# shield.net
KiCad netlist of a schematic drawn in EAGLE
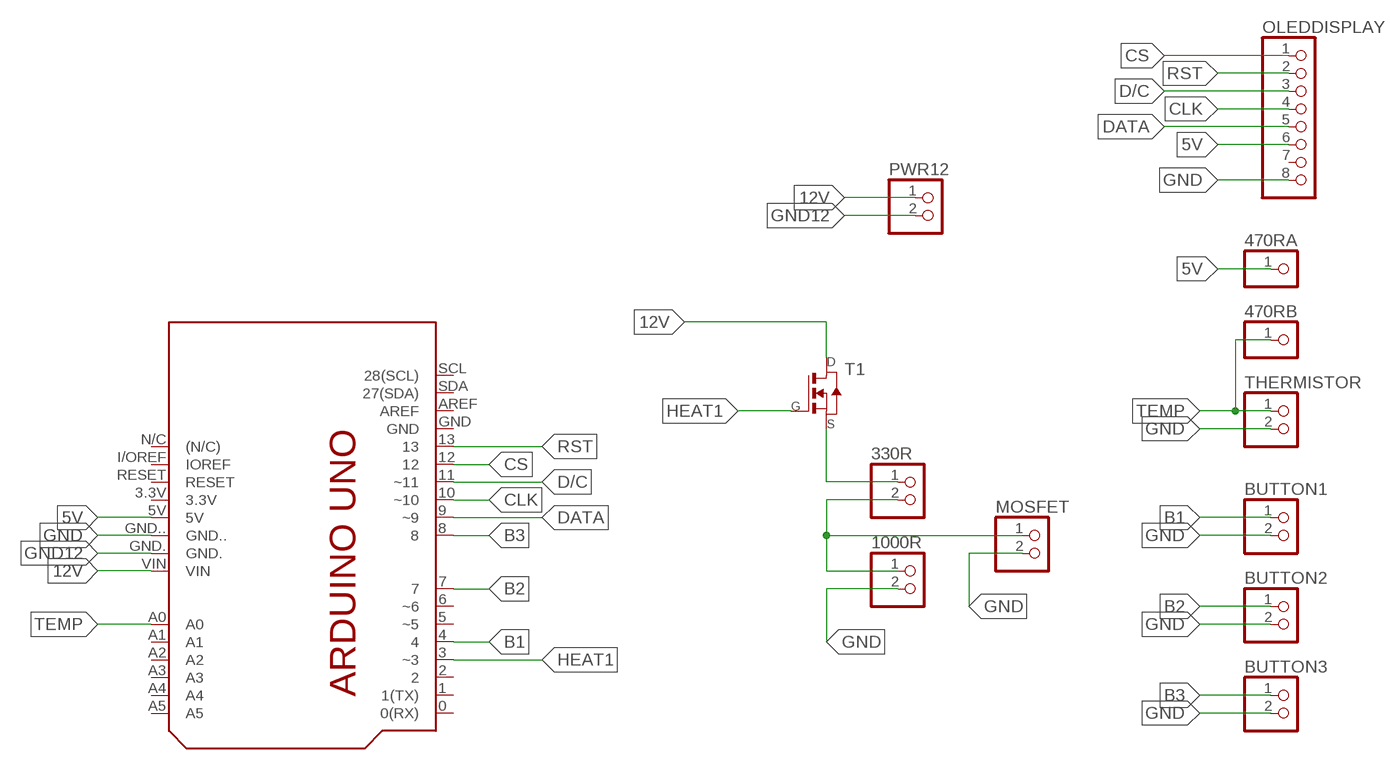
[diagram p0: schematic, sheet 1]

(export (version "E")
  (design (tool "Eeschema 10.0.6"))
  (components
    (comp (ref "330R")
      (value "PINHD-1X2")
      (footprint "eagle-import:1X02")
      (libsource (lib "eagle-import") (part "PINHD-1X2"))
    )
    (comp (ref "470RA")
      (value "PINHD-1X1")
      (footprint "eagle-import:1X01")
      (libsource (lib "eagle-import") (part "PINHD-1X1"))
    )
    (comp (ref "470RB")
      (value "PINHD-1X1")
      (footprint "eagle-import:1X01")
      (libsource (lib "eagle-import") (part "PINHD-1X1"))
    )
    (comp (ref "1000R")
      (value "PINHD-1X2")
      (footprint "eagle-import:1X02")
      (libsource (lib "eagle-import") (part "PINHD-1X2"))
    )
    (comp (ref "BUTTON1")
      (value "PINHD-1X2")
      (footprint "eagle-import:1X02")
      (libsource (lib "eagle-import") (part "PINHD-1X2"))
    )
    (comp (ref "BUTTON2")
      (value "PINHD-1X2")
      (footprint "eagle-import:1X02")
      (libsource (lib "eagle-import") (part "PINHD-1X2"))
    )
    (comp (ref "BUTTON3")
      (value "PINHD-1X2")
      (footprint "eagle-import:1X02")
      (libsource (lib "eagle-import") (part "PINHD-1X2"))
    )
    (comp (ref "MOSFET")
      (value "PINHD-1X2")
      (footprint "eagle-import:1X02")
      (libsource (lib "eagle-import") (part "PINHD-1X2"))
    )
    (comp (ref "OLEDDISPLAY")
      (value "PINHD-1X8")
      (footprint "eagle-import:1X08")
      (libsource (lib "eagle-import") (part "PINHD-1X8"))
    )
    (comp (ref "PCB1")
      (value "ARDUINO_UNO_UNBOUND")
      (footprint "eagle-import:ARDUINO_UNO_UNBOUND")
      (libsource (lib "eagle-import") (part "ARDUINO_UNO_UNBOUND"))
    )
    (comp (ref "PWR12")
      (value "PINHD-1X2")
      (footprint "eagle-import:1X02")
      (libsource (lib "eagle-import") (part "PINHD-1X2"))
    )
    (comp (ref "T1")
      (value "NMOSFETTO252")
      (footprint "eagle-import:TO252")
      (libsource (lib "eagle-import") (part "NMOSFETTO252"))
    )
    (comp (ref "THERMISTOR")
      (value "PINHD-1X2")
      (footprint "eagle-import:1X02")
      (libsource (lib "eagle-import") (part "PINHD-1X2"))
    )
  )
  (nets
    (net (code "1") (name "5V") (class "Default")
      (node (ref "470RA") (pin "1") (pinfunction "1_1") (pintype "passive"))
      (node (ref "OLEDDISPLAY") (pin "6") (pinfunction "6_6") (pintype "passive"))
      (node (ref "PCB1") (pin "5V") (pinfunction "5V_5V") (pintype "bidirectional"))
    )
    (net (code "2") (name "12V") (class "Default")
      (node (ref "PCB1") (pin "VIN") (pinfunction "VIN_VIN") (pintype "bidirectional"))
      (node (ref "PWR12") (pin "1") (pinfunction "1_1") (pintype "passive"))
      (node (ref "T1") (pin "3") (pinfunction "D_3") (pintype "passive"))
    )
    (net (code "3") (name "B1") (class "Default")
      (node (ref "BUTTON1") (pin "1") (pinfunction "1_1") (pintype "passive"))
      (node (ref "PCB1") (pin "4") (pinfunction "4_4") (pintype "bidirectional"))
    )
    (net (code "4") (name "B2") (class "Default")
      (node (ref "BUTTON2") (pin "1") (pinfunction "1_1") (pintype "passive"))
      (node (ref "PCB1") (pin "7") (pinfunction "7_7") (pintype "bidirectional"))
    )
    (net (code "5") (name "B3") (class "Default")
      (node (ref "BUTTON3") (pin "1") (pinfunction "1_1") (pintype "passive"))
      (node (ref "PCB1") (pin "8") (pinfunction "8_8") (pintype "bidirectional"))
    )
    (net (code "6") (name "CLK") (class "Default")
      (node (ref "OLEDDISPLAY") (pin "4") (pinfunction "4_4") (pintype "passive"))
      (node (ref "PCB1") (pin "10") (pinfunction "~{10}_10") (pintype "bidirectional"))
    )
    (net (code "7") (name "CS") (class "Default")
      (node (ref "OLEDDISPLAY") (pin "1") (pinfunction "1_1") (pintype "passive"))
      (node (ref "PCB1") (pin "12") (pinfunction "12_12") (pintype "bidirectional"))
    )
    (net (code "8") (name "DATA") (class "Default")
      (node (ref "OLEDDISPLAY") (pin "5") (pinfunction "5_5") (pintype "passive"))
      (node (ref "PCB1") (pin "9") (pinfunction "~{9}_9") (pintype "bidirectional"))
    )
    (net (code "9") (name "D{slash}C") (class "Default")
      (node (ref "OLEDDISPLAY") (pin "3") (pinfunction "3_3") (pintype "passive"))
      (node (ref "PCB1") (pin "11") (pinfunction "~{11}_11") (pintype "bidirectional"))
    )
    (net (code "10") (name "GND") (class "Default")
      (node (ref "1000R") (pin "2") (pinfunction "2_2") (pintype "passive"))
      (node (ref "BUTTON1") (pin "2") (pinfunction "2_2") (pintype "passive"))
      (node (ref "BUTTON2") (pin "2") (pinfunction "2_2") (pintype "passive"))
      (node (ref "BUTTON3") (pin "2") (pinfunction "2_2") (pintype "passive"))
      (node (ref "MOSFET") (pin "2") (pinfunction "2_2") (pintype "passive"))
      (node (ref "OLEDDISPLAY") (pin "8") (pinfunction "8_8") (pintype "passive"))
      (node (ref "PCB1") (pin "GND..") (pinfunction "GND.._GND..") (pintype "bidirectional"))
      (node (ref "THERMISTOR") (pin "2") (pinfunction "2_2") (pintype "passive"))
    )
    (net (code "11") (name "GND12") (class "Default")
      (node (ref "PCB1") (pin "GND.") (pinfunction "GND._GND.") (pintype "bidirectional"))
      (node (ref "PWR12") (pin "2") (pinfunction "2_2") (pintype "passive"))
    )
    (net (code "12") (name "HEAT1") (class "Default")
      (node (ref "PCB1") (pin "3") (pinfunction "~{3}_3") (pintype "bidirectional"))
      (node (ref "T1") (pin "1") (pinfunction "G_1") (pintype "passive"))
    )
    (net (code "13") (name "Net-(1000R-Pad1)") (class "Default")
      (node (ref "1000R") (pin "1") (pinfunction "1_1") (pintype "passive"))
      (node (ref "330R") (pin "2") (pinfunction "2_2") (pintype "passive"))
      (node (ref "MOSFET") (pin "1") (pinfunction "1_1") (pintype "passive"))
    )
    (net (code "14") (name "Net-(T1-S)") (class "Default")
      (node (ref "330R") (pin "1") (pinfunction "1_1") (pintype "passive"))
      (node (ref "T1") (pin "2") (pinfunction "S_2") (pintype "passive"))
    )
    (net (code "15") (name "RST") (class "Default")
      (node (ref "OLEDDISPLAY") (pin "2") (pinfunction "2_2") (pintype "passive"))
      (node (ref "PCB1") (pin "13") (pinfunction "13_13") (pintype "bidirectional"))
    )
    (net (code "16") (name "TEMP") (class "Default")
      (node (ref "470RB") (pin "1") (pinfunction "1_1") (pintype "passive"))
      (node (ref "PCB1") (pin "A0") (pinfunction "A0_A0") (pintype "bidirectional"))
      (node (ref "THERMISTOR") (pin "1") (pinfunction "1_1") (pintype "passive"))
    )
    (net (code "17") (name "unconnected-(OLEDDISPLAY-Pad7)") (class "Default")
      (node (ref "OLEDDISPLAY") (pin "7") (pinfunction "7_7") (pintype "passive"))
    )
    (net (code "18") (name "unconnected-(PCB1-(N{slash}C)-PadN{slash}C)") (class "Default")
      (node (ref "PCB1") (pin "N/C") (pinfunction "(N/C)_N/C") (pintype "bidirectional"))
    )
    (net (code "19") (name "unconnected-(PCB1-0(RX)-Pad0)") (class "Default")
      (node (ref "PCB1") (pin "0") (pinfunction "0(RX)_0") (pintype "bidirectional"))
    )
    (net (code "20") (name "unconnected-(PCB1-1(TX)-Pad1)") (class "Default")
      (node (ref "PCB1") (pin "1") (pinfunction "1(TX)_1") (pintype "bidirectional"))
    )
    (net (code "21") (name "unconnected-(PCB1-27(SDA)-PadSDA)") (class "Default")
      (node (ref "PCB1") (pin "SDA") (pinfunction "27(SDA)_SDA") (pintype "bidirectional"))
    )
    (net (code "22") (name "unconnected-(PCB1-28(SCL)-PadSCL)") (class "Default")
      (node (ref "PCB1") (pin "SCL") (pinfunction "28(SCL)_SCL") (pintype "bidirectional"))
    )
    (net (code "23") (name "unconnected-(PCB1-IOREF-PadI{slash}OREF)") (class "Default")
      (node (ref "PCB1") (pin "I/OREF") (pinfunction "IOREF_I/OREF") (pintype "bidirectional"))
    )
    (net (code "24") (name "unconnected-(PCB1-Pad2)") (class "Default")
      (node (ref "PCB1") (pin "2") (pinfunction "2_2") (pintype "bidirectional"))
    )
    (net (code "25") (name "unconnected-(PCB1-Pad3.3V)") (class "Default")
      (node (ref "PCB1") (pin "3.3V") (pinfunction "3.3V_3.3V") (pintype "bidirectional"))
    )
    (net (code "26") (name "unconnected-(PCB1-PadA1)") (class "Default")
      (node (ref "PCB1") (pin "A1") (pinfunction "A1_A1") (pintype "bidirectional"))
    )
    (net (code "27") (name "unconnected-(PCB1-PadA2)") (class "Default")
      (node (ref "PCB1") (pin "A2") (pinfunction "A2_A2") (pintype "bidirectional"))
    )
    (net (code "28") (name "unconnected-(PCB1-PadA3)") (class "Default")
      (node (ref "PCB1") (pin "A3") (pinfunction "A3_A3") (pintype "bidirectional"))
    )
    (net (code "29") (name "unconnected-(PCB1-PadA4)") (class "Default")
      (node (ref "PCB1") (pin "A4") (pinfunction "A4_A4") (pintype "bidirectional"))
    )
    (net (code "30") (name "unconnected-(PCB1-PadA5)") (class "Default")
      (node (ref "PCB1") (pin "A5") (pinfunction "A5_A5") (pintype "bidirectional"))
    )
    (net (code "31") (name "unconnected-(PCB1-PadAREF)") (class "Default")
      (node (ref "PCB1") (pin "AREF") (pinfunction "AREF_AREF") (pintype "bidirectional"))
    )
    (net (code "32") (name "unconnected-(PCB1-PadGND)") (class "Default")
      (node (ref "PCB1") (pin "GND") (pinfunction "GND_GND") (pintype "bidirectional"))
    )
    (net (code "33") (name "unconnected-(PCB1-PadRESET)") (class "Default")
      (node (ref "PCB1") (pin "RESET") (pinfunction "RESET_RESET") (pintype "bidirectional"))
    )
    (net (code "34") (name "unconnected-(PCB1-~{5}-Pad5)") (class "Default")
      (node (ref "PCB1") (pin "5") (pinfunction "~{5}_5") (pintype "bidirectional"))
    )
    (net (code "35") (name "unconnected-(PCB1-~{6}-Pad6)") (class "Default")
      (node (ref "PCB1") (pin "6") (pinfunction "~{6}_6") (pintype "bidirectional"))
    )
  )
)
